# Heating.net
KiCad netlist of a schematic drawn in Altium Designer
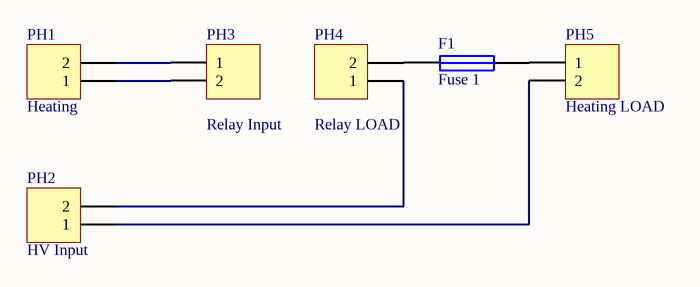
[diagram p0: Heating.SchDoc]

(export (version "E")
  (design (tool "Eeschema 10.0.6"))
  (components
    (comp (ref "F1")
      (value "Fuse 1")
      (footprint "PIN-W2/E2.8")
      (description "Fuse")
      (fields (field (name "PUBLISHER") "Altium Limited"))
      (libsource (lib "Miscellaneous Devices") (part "Fuse 1"))
    )
    (comp (ref "PH1")
      (value "Heating")
      (footprint "HDR1X2")
      (description "Header, 2-Pin")
      (fields (field (name "PUBLISHER") "Altium Limited"))
      (libsource (lib "") (part "Header 2_1"))
    )
    (comp (ref "PH2")
      (value "HV Input")
      (footprint "HDR1X2")
      (description "Header, 2-Pin")
      (fields (field (name "PUBLISHER") "Altium Limited"))
      (libsource (lib "") (part "Header 2_1"))
    )
    (comp (ref "PH3")
      (value "Relay Input")
      (footprint "HDR1X2")
      (description "Header, 2-Pin")
      (fields (field (name "PUBLISHER") "Altium Limited"))
      (libsource (lib "Miscellaneous Connectors") (part "Header 2"))
    )
    (comp (ref "PH4")
      (value "Relay LOAD")
      (footprint "HDR1X2")
      (description "Header, 2-Pin")
      (fields (field (name "PUBLISHER") "Altium Limited"))
      (libsource (lib "") (part "Header 2_1"))
    )
    (comp (ref "PH5")
      (value "Heating LOAD")
      (footprint "HDR1X2")
      (description "Header, 2-Pin")
      (fields (field (name "PUBLISHER") "Altium Limited"))
      (libsource (lib "Miscellaneous Connectors") (part "Header 2"))
    )
  )
  (nets
    (net (code "1") (name "Net-(F1-Pad1)") (class "Default")
      (node (ref "F1") (pin "1") (pinfunction "1_1") (pintype "passive"))
      (node (ref "PH4") (pin "2") (pinfunction "2_2") (pintype "passive"))
    )
    (net (code "2") (name "Net-(F1-Pad2)") (class "Default")
      (node (ref "F1") (pin "2") (pinfunction "2_2") (pintype "passive"))
      (node (ref "PH5") (pin "1") (pinfunction "1_1") (pintype "passive"))
    )
    (net (code "3") (name "Net-(PH1-Pad1)") (class "Default")
      (node (ref "PH1") (pin "1") (pinfunction "1_1") (pintype "passive"))
      (node (ref "PH3") (pin "2") (pinfunction "2_2") (pintype "passive"))
    )
    (net (code "4") (name "Net-(PH1-Pad2)") (class "Default")
      (node (ref "PH1") (pin "2") (pinfunction "2_2") (pintype "passive"))
      (node (ref "PH3") (pin "1") (pinfunction "1_1") (pintype "passive"))
    )
    (net (code "5") (name "Net-(PH2-Pad1)") (class "Default")
      (node (ref "PH2") (pin "1") (pinfunction "1_1") (pintype "passive"))
      (node (ref "PH5") (pin "2") (pinfunction "2_2") (pintype "passive"))
    )
    (net (code "6") (name "Net-(PH2-Pad2)") (class "Default")
      (node (ref "PH2") (pin "2") (pinfunction "2_2") (pintype "passive"))
      (node (ref "PH4") (pin "1") (pinfunction "1_1") (pintype "passive"))
    )
  )
)
